# yogasanyoto.net
KiCad netlist of a schematic drawn in EAGLE
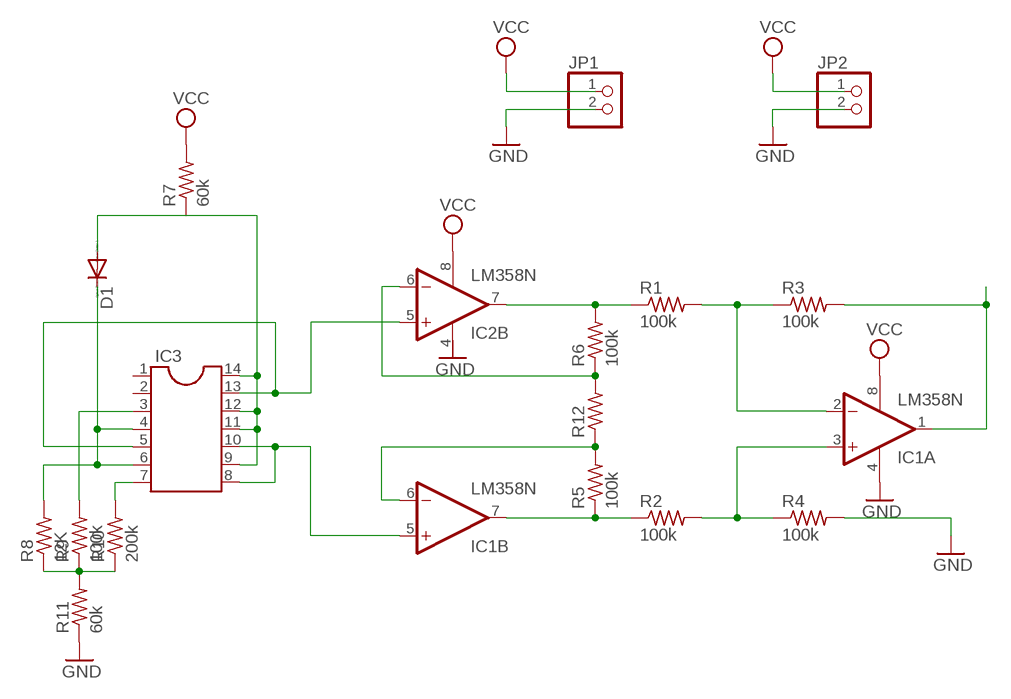
[diagram p0: schematic, sheet 1]

(export (version "E")
  (design (tool "Eeschema 10.0.6"))
  (components
    (comp (ref "D1")
      (value "DIODE-D-7.5")
      (footprint "eagle-import:D-7.5")
      (libsource (lib "eagle-import") (part "DIODE-D-7.5"))
    )
    (comp (ref "IC1")
      (value "LM358N")
      (footprint "eagle-import:DIL08")
      (libsource (lib "eagle-import") (part "LM358N"))
    )
    (comp (ref "IC2")
      (value "LM358N")
      (footprint "eagle-import:DIL08")
      (libsource (lib "eagle-import") (part "LM358N"))
    )
    (comp (ref "IC3")
      (value "DIL14")
      (footprint "eagle-import:DIL14")
      (libsource (lib "eagle-import") (part "DIL14"))
    )
    (comp (ref "JP1")
      (value "PINHD-1X2")
      (footprint "eagle-import:1X02")
      (libsource (lib "eagle-import") (part "PINHD-1X2"))
    )
    (comp (ref "JP2")
      (value "PINHD-1X2")
      (footprint "eagle-import:1X02")
      (libsource (lib "eagle-import") (part "PINHD-1X2"))
    )
    (comp (ref "R1")
      (value "100k")
      (footprint "eagle-import:0204_7")
      (libsource (lib "eagle-import") (part "R-US_0204/7"))
    )
    (comp (ref "R2")
      (value "100k")
      (footprint "eagle-import:0204_7")
      (libsource (lib "eagle-import") (part "R-US_0204/7"))
    )
    (comp (ref "R3")
      (value "100k")
      (footprint "eagle-import:0204_7")
      (libsource (lib "eagle-import") (part "R-US_0204/7"))
    )
    (comp (ref "R4")
      (value "100k")
      (footprint "eagle-import:0204_7")
      (libsource (lib "eagle-import") (part "R-US_0204/7"))
    )
    (comp (ref "R5")
      (value "100k")
      (footprint "eagle-import:0204_7")
      (libsource (lib "eagle-import") (part "R-US_0204/7"))
    )
    (comp (ref "R6")
      (value "100k")
      (footprint "eagle-import:0204_7")
      (libsource (lib "eagle-import") (part "R-US_0204/7"))
    )
    (comp (ref "R7")
      (value "60k")
      (footprint "eagle-import:0204_7")
      (libsource (lib "eagle-import") (part "R-US_0204/7"))
    )
    (comp (ref "R8")
      (value "12K")
      (footprint "eagle-import:0204_7")
      (libsource (lib "eagle-import") (part "R-US_0204/7"))
    )
    (comp (ref "R9")
      (value "100k")
      (footprint "eagle-import:0204_7")
      (libsource (lib "eagle-import") (part "R-US_0204/7"))
    )
    (comp (ref "R10")
      (value "200k")
      (footprint "eagle-import:0204_7")
      (libsource (lib "eagle-import") (part "R-US_0204/7"))
    )
    (comp (ref "R11")
      (value "60k")
      (footprint "eagle-import:0204_7")
      (libsource (lib "eagle-import") (part "R-US_0204/7"))
    )
    (comp (ref "R12")
      (value "R-US_0204/7")
      (footprint "eagle-import:0204_7")
      (libsource (lib "eagle-import") (part "R-US_0204/7"))
    )
  )
  (nets
    (net (code "1") (name "/V-") (class "Default")
      (node (ref "IC2") (pin "4") (pinfunction "V-_4") (pintype "power_in"))
    )
    (net (code "2") (name "GND") (class "Default")
      (node (ref "IC1") (pin "4") (pinfunction "V-_4") (pintype "power_in"))
      (node (ref "JP1") (pin "2") (pinfunction "2_2") (pintype "passive"))
      (node (ref "JP2") (pin "2") (pinfunction "2_2") (pintype "passive"))
      (node (ref "R11") (pin "1") (pinfunction "1_1") (pintype "passive"))
      (node (ref "R4") (pin "2") (pinfunction "2_2") (pintype "passive"))
    )
    (net (code "3") (name "Net-(D1-PadA)") (class "Default")
      (node (ref "D1") (pin "A") (pinfunction "A_A") (pintype "passive"))
      (node (ref "IC3") (pin "11") (pinfunction "11_11") (pintype "passive"))
      (node (ref "IC3") (pin "12") (pinfunction "12_12") (pintype "passive"))
      (node (ref "IC3") (pin "14") (pinfunction "14_14") (pintype "passive"))
      (node (ref "IC3") (pin "9") (pinfunction "9_9") (pintype "passive"))
      (node (ref "R7") (pin "1") (pinfunction "1_1") (pintype "passive"))
    )
    (net (code "4") (name "Net-(D1-PadC)") (class "Default")
      (node (ref "D1") (pin "C") (pinfunction "C_C") (pintype "passive"))
      (node (ref "IC3") (pin "4") (pinfunction "4_4") (pintype "passive"))
      (node (ref "IC3") (pin "6") (pinfunction "6_6") (pintype "passive"))
      (node (ref "R8") (pin "2") (pinfunction "2_2") (pintype "passive"))
    )
    (net (code "5") (name "Net-(IC1A-+IN)") (class "Default")
      (node (ref "IC1") (pin "3") (pinfunction "+IN_3") (pintype "input"))
      (node (ref "R2") (pin "2") (pinfunction "2_2") (pintype "passive"))
      (node (ref "R4") (pin "1") (pinfunction "1_1") (pintype "passive"))
    )
    (net (code "6") (name "Net-(IC1A--IN)") (class "Default")
      (node (ref "IC1") (pin "2") (pinfunction "-IN_2") (pintype "input"))
      (node (ref "R1") (pin "2") (pinfunction "2_2") (pintype "passive"))
      (node (ref "R3") (pin "1") (pinfunction "1_1") (pintype "passive"))
    )
    (net (code "7") (name "Net-(IC1A-OUT)") (class "Default")
      (node (ref "IC1") (pin "1") (pinfunction "OUT_1") (pintype "output"))
      (node (ref "R3") (pin "2") (pinfunction "2_2") (pintype "passive"))
    )
    (net (code "8") (name "Net-(IC1B-+IN)") (class "Default")
      (node (ref "IC1") (pin "5") (pinfunction "+IN_5") (pintype "input"))
      (node (ref "IC3") (pin "10") (pinfunction "10_10") (pintype "passive"))
      (node (ref "IC3") (pin "8") (pinfunction "8_8") (pintype "passive"))
    )
    (net (code "9") (name "Net-(IC1B--IN)") (class "Default")
      (node (ref "IC1") (pin "6") (pinfunction "-IN_6") (pintype "input"))
      (node (ref "R12") (pin "1") (pinfunction "1_1") (pintype "passive"))
      (node (ref "R5") (pin "2") (pinfunction "2_2") (pintype "passive"))
    )
    (net (code "10") (name "Net-(IC1B-OUT)") (class "Default")
      (node (ref "IC1") (pin "7") (pinfunction "OUT_7") (pintype "output"))
      (node (ref "R2") (pin "1") (pinfunction "1_1") (pintype "passive"))
      (node (ref "R5") (pin "1") (pinfunction "1_1") (pintype "passive"))
    )
    (net (code "11") (name "Net-(IC2B-+IN)") (class "Default")
      (node (ref "IC2") (pin "5") (pinfunction "+IN_5") (pintype "input"))
      (node (ref "IC3") (pin "13") (pinfunction "13_13") (pintype "passive"))
      (node (ref "IC3") (pin "5") (pinfunction "5_5") (pintype "passive"))
    )
    (net (code "12") (name "Net-(IC2B--IN)") (class "Default")
      (node (ref "IC2") (pin "6") (pinfunction "-IN_6") (pintype "input"))
      (node (ref "R12") (pin "2") (pinfunction "2_2") (pintype "passive"))
      (node (ref "R6") (pin "1") (pinfunction "1_1") (pintype "passive"))
    )
    (net (code "13") (name "Net-(IC2B-OUT)") (class "Default")
      (node (ref "IC2") (pin "7") (pinfunction "OUT_7") (pintype "output"))
      (node (ref "R1") (pin "1") (pinfunction "1_1") (pintype "passive"))
      (node (ref "R6") (pin "2") (pinfunction "2_2") (pintype "passive"))
    )
    (net (code "14") (name "Net-(IC3-Pad3)") (class "Default")
      (node (ref "IC3") (pin "3") (pinfunction "3_3") (pintype "passive"))
      (node (ref "R9") (pin "2") (pinfunction "2_2") (pintype "passive"))
    )
    (net (code "15") (name "Net-(IC3-Pad7)") (class "Default")
      (node (ref "IC3") (pin "7") (pinfunction "7_7") (pintype "passive"))
      (node (ref "R10") (pin "2") (pinfunction "2_2") (pintype "passive"))
    )
    (net (code "16") (name "Net-(R10-Pad1)") (class "Default")
      (node (ref "R10") (pin "1") (pinfunction "1_1") (pintype "passive"))
      (node (ref "R11") (pin "2") (pinfunction "2_2") (pintype "passive"))
      (node (ref "R8") (pin "1") (pinfunction "1_1") (pintype "passive"))
      (node (ref "R9") (pin "1") (pinfunction "1_1") (pintype "passive"))
    )
    (net (code "17") (name "VCC") (class "Default")
      (node (ref "IC1") (pin "8") (pinfunction "V+_8") (pintype "power_in"))
      (node (ref "IC2") (pin "8") (pinfunction "V+_8") (pintype "power_in"))
      (node (ref "JP1") (pin "1") (pinfunction "1_1") (pintype "passive"))
      (node (ref "JP2") (pin "1") (pinfunction "1_1") (pintype "passive"))
      (node (ref "R7") (pin "2") (pinfunction "2_2") (pintype "passive"))
    )
    (net (code "18") (name "unconnected-(IC3-Pad1)") (class "Default")
      (node (ref "IC3") (pin "1") (pinfunction "1_1") (pintype "passive"))
    )
    (net (code "19") (name "unconnected-(IC3-Pad2)") (class "Default")
      (node (ref "IC3") (pin "2") (pinfunction "2_2") (pintype "passive"))
    )
  )
)
